# AbercrombieBlockage2.net
KiCad netlist of a schematic drawn in EAGLE
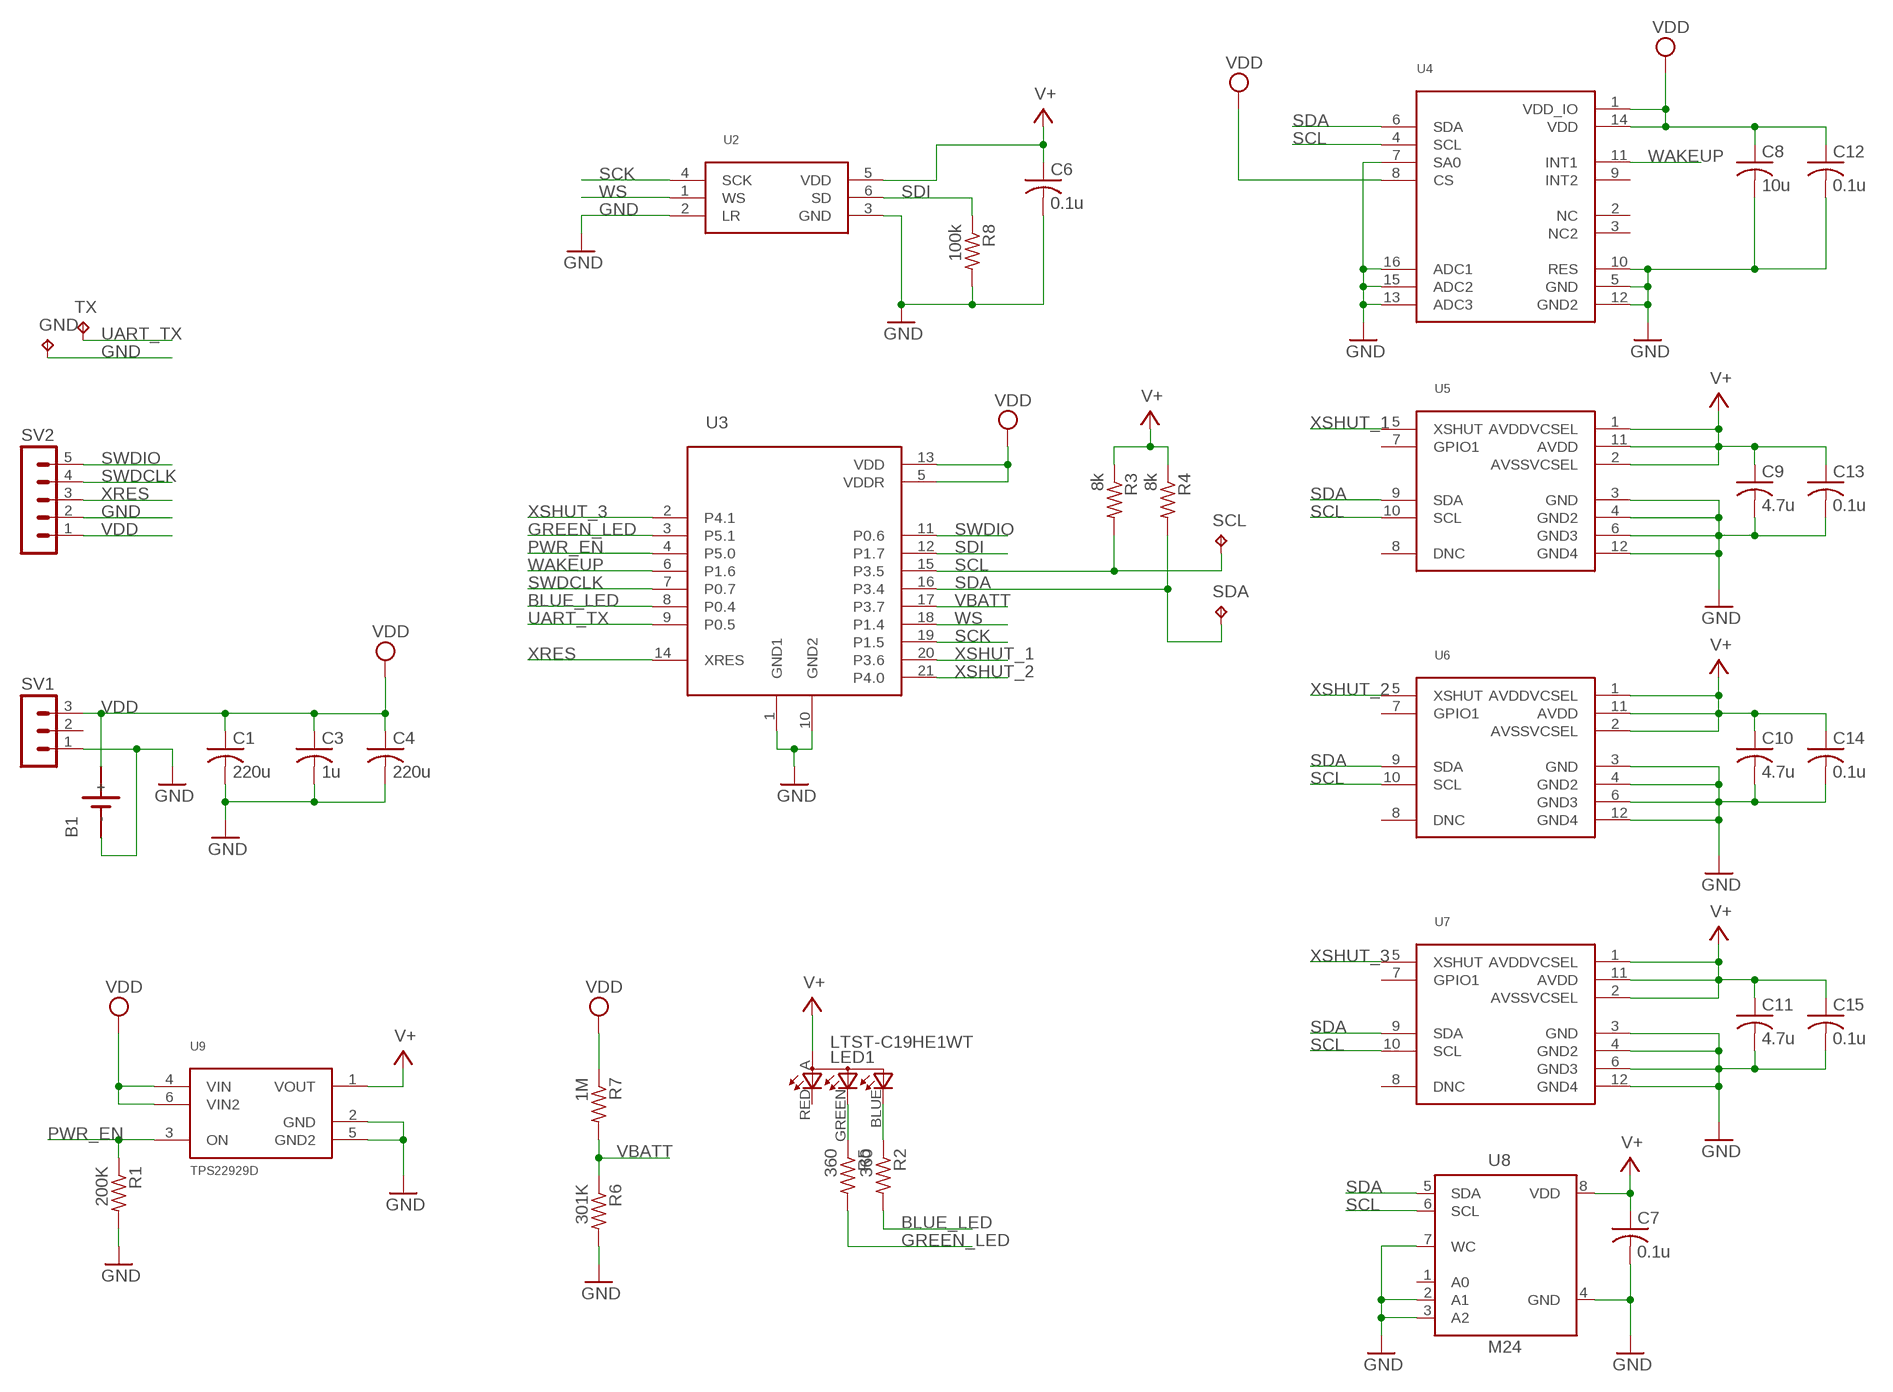
[diagram p0: schematic, sheet 1]

(export (version "E")
  (design (tool "Eeschema 10.0.6"))
  (components
    (comp (ref "B1")
      (value "BU2032")
      (footprint "eagle-import:BU2032")
      (libsource (lib "eagle-import") (part "BU2032"))
    )
    (comp (ref "C1")
      (value "220u")
      (footprint "eagle-import:C1210")
      (libsource (lib "eagle-import") (part "C-USC1210"))
    )
    (comp (ref "C3")
      (value "1u")
      (footprint "eagle-import:C0603")
      (libsource (lib "eagle-import") (part "C-USC0603"))
    )
    (comp (ref "C4")
      (value "220u")
      (footprint "eagle-import:C1210")
      (libsource (lib "eagle-import") (part "C-USC1210"))
    )
    (comp (ref "C6")
      (value "0.1u")
      (footprint "eagle-import:C0603")
      (libsource (lib "eagle-import") (part "C-USC0603"))
    )
    (comp (ref "C7")
      (value "0.1u")
      (footprint "eagle-import:C0603")
      (libsource (lib "eagle-import") (part "C-USC0603"))
    )
    (comp (ref "C8")
      (value "10u")
      (footprint "eagle-import:C0603")
      (libsource (lib "eagle-import") (part "C-USC0603"))
    )
    (comp (ref "C9")
      (value "4.7u")
      (footprint "eagle-import:C0603")
      (libsource (lib "eagle-import") (part "C-USC0603"))
    )
    (comp (ref "C10")
      (value "4.7u")
      (footprint "eagle-import:C0603")
      (libsource (lib "eagle-import") (part "C-USC0603"))
    )
    (comp (ref "C11")
      (value "4.7u")
      (footprint "eagle-import:C0603")
      (libsource (lib "eagle-import") (part "C-USC0603"))
    )
    (comp (ref "C12")
      (value "0.1u")
      (footprint "eagle-import:C0603")
      (libsource (lib "eagle-import") (part "C-USC0603"))
    )
    (comp (ref "C13")
      (value "0.1u")
      (footprint "eagle-import:C0603")
      (libsource (lib "eagle-import") (part "C-USC0603"))
    )
    (comp (ref "C14")
      (value "0.1u")
      (footprint "eagle-import:C0603")
      (libsource (lib "eagle-import") (part "C-USC0603"))
    )
    (comp (ref "C15")
      (value "0.1u")
      (footprint "eagle-import:C0603")
      (libsource (lib "eagle-import") (part "C-USC0603"))
    )
    (comp (ref "GND")
      (value "TPB1,27")
      (footprint "eagle-import:B1,27")
      (libsource (lib "eagle-import") (part "TPB1,27"))
    )
    (comp (ref "LED1")
      (value "LTST-C19HE1WT")
      (footprint "eagle-import:LTST-C19HE1WT")
      (libsource (lib "eagle-import") (part "LTST-C19HE1WT"))
    )
    (comp (ref "R1")
      (value "200K")
      (footprint "eagle-import:R0603")
      (libsource (lib "eagle-import") (part "R-US_R0603"))
    )
    (comp (ref "R2")
      (value "360")
      (footprint "eagle-import:R0603")
      (libsource (lib "eagle-import") (part "R-US_R0603"))
    )
    (comp (ref "R3")
      (value "8k")
      (footprint "eagle-import:R0603")
      (libsource (lib "eagle-import") (part "R-US_R0603"))
    )
    (comp (ref "R4")
      (value "8k")
      (footprint "eagle-import:R0603")
      (libsource (lib "eagle-import") (part "R-US_R0603"))
    )
    (comp (ref "R5")
      (value "360")
      (footprint "eagle-import:R0603")
      (libsource (lib "eagle-import") (part "R-US_R0603"))
    )
    (comp (ref "R6")
      (value "301K")
      (footprint "eagle-import:R0603")
      (libsource (lib "eagle-import") (part "R-US_R0603"))
    )
    (comp (ref "R7")
      (value "1M")
      (footprint "eagle-import:R0603")
      (libsource (lib "eagle-import") (part "R-US_R0603"))
    )
    (comp (ref "R8")
      (value "100k")
      (footprint "eagle-import:R0603")
      (libsource (lib "eagle-import") (part "R-US_R0603"))
    )
    (comp (ref "SCL")
      (value "TPB1,27")
      (footprint "eagle-import:B1,27")
      (libsource (lib "eagle-import") (part "TPB1,27"))
    )
    (comp (ref "SDA")
      (value "TPB1,27")
      (footprint "eagle-import:B1,27")
      (libsource (lib "eagle-import") (part "TPB1,27"))
    )
    (comp (ref "SV1")
      (value "MA03-1")
      (footprint "eagle-import:MA03-1")
      (libsource (lib "eagle-import") (part "MA03-1"))
    )
    (comp (ref "SV2")
      (value "MA05-1")
      (footprint "eagle-import:MA05-1")
      (libsource (lib "eagle-import") (part "MA05-1"))
    )
    (comp (ref "TX")
      (value "TPB1,27")
      (footprint "eagle-import:B1,27")
      (libsource (lib "eagle-import") (part "TPB1,27"))
    )
    (comp (ref "U2")
      (value "ICS-43434")
      (footprint "eagle-import:ICS-43434")
      (libsource (lib "eagle-import") (part "ICS-43434"))
    )
    (comp (ref "U3")
      (value "CYBLE-022001-00")
      (footprint "eagle-import:CYBLE-022001-00")
      (libsource (lib "eagle-import") (part "CYBLE-022001-00"))
    )
    (comp (ref "U4")
      (value "LIS3DH")
      (footprint "eagle-import:LGA-16")
      (libsource (lib "eagle-import") (part "LIS3DH"))
    )
    (comp (ref "U5")
      (value "VL53L0X")
      (footprint "eagle-import:VL53L0X")
      (libsource (lib "eagle-import") (part "VL53L0X"))
    )
    (comp (ref "U6")
      (value "VL53L0X")
      (footprint "eagle-import:VL53L0X")
      (libsource (lib "eagle-import") (part "VL53L0X"))
    )
    (comp (ref "U7")
      (value "VL53L0X")
      (footprint "eagle-import:VL53L0X")
      (libsource (lib "eagle-import") (part "VL53L0X"))
    )
    (comp (ref "U8")
      (value "M24")
      (footprint "eagle-import:SO-08")
      (libsource (lib "eagle-import") (part "M24"))
    )
    (comp (ref "U9")
      (value "TPS22929D")
      (footprint "eagle-import:SOT-23-6")
      (libsource (lib "eagle-import") (part "TPS22929D"))
    )
  )
  (nets
    (net (code "1") (name "/BLUE_LED") (class "Default")
      (node (ref "R2") (pin "2") (pinfunction "2_2") (pintype "passive"))
      (node (ref "U3") (pin "8") (pinfunction "P0.4_8") (pintype "bidirectional"))
    )
    (net (code "2") (name "/GREEN_LED") (class "Default")
      (node (ref "R5") (pin "2") (pinfunction "2_2") (pintype "passive"))
      (node (ref "U3") (pin "3") (pinfunction "P5.1_3") (pintype "bidirectional"))
    )
    (net (code "3") (name "/PWR_EN") (class "Default")
      (node (ref "R1") (pin "1") (pinfunction "1_1") (pintype "passive"))
      (node (ref "U3") (pin "4") (pinfunction "P5.0_4") (pintype "bidirectional"))
      (node (ref "U9") (pin "3") (pinfunction "ON_3") (pintype "bidirectional"))
    )
    (net (code "4") (name "/SCK") (class "Default")
      (node (ref "U2") (pin "4") (pinfunction "SCK_4") (pintype "bidirectional"))
      (node (ref "U3") (pin "19") (pinfunction "P1.5_19") (pintype "bidirectional"))
    )
    (net (code "5") (name "/SCL") (class "Default")
      (node (ref "R3") (pin "2") (pinfunction "2_2") (pintype "passive"))
      (node (ref "SCL") (pin "TP") (pinfunction "TP_TP") (pintype "input"))
      (node (ref "U3") (pin "15") (pinfunction "P3.5_15") (pintype "bidirectional"))
      (node (ref "U4") (pin "4") (pinfunction "SCL_4") (pintype "bidirectional"))
      (node (ref "U5") (pin "10") (pinfunction "SCL_10") (pintype "bidirectional"))
      (node (ref "U6") (pin "10") (pinfunction "SCL_10") (pintype "bidirectional"))
      (node (ref "U7") (pin "10") (pinfunction "SCL_10") (pintype "bidirectional"))
      (node (ref "U8") (pin "6") (pinfunction "SCL_6") (pintype "input"))
    )
    (net (code "6") (name "/SDA") (class "Default")
      (node (ref "R4") (pin "2") (pinfunction "2_2") (pintype "passive"))
      (node (ref "SDA") (pin "TP") (pinfunction "TP_TP") (pintype "input"))
      (node (ref "U3") (pin "16") (pinfunction "P3.4_16") (pintype "bidirectional"))
      (node (ref "U4") (pin "6") (pinfunction "SDA_6") (pintype "bidirectional"))
      (node (ref "U5") (pin "9") (pinfunction "SDA_9") (pintype "bidirectional"))
      (node (ref "U6") (pin "9") (pinfunction "SDA_9") (pintype "bidirectional"))
      (node (ref "U7") (pin "9") (pinfunction "SDA_9") (pintype "bidirectional"))
      (node (ref "U8") (pin "5") (pinfunction "SDA_5") (pintype "bidirectional"))
    )
    (net (code "7") (name "/SDI") (class "Default")
      (node (ref "R8") (pin "1") (pinfunction "1_1") (pintype "passive"))
      (node (ref "U2") (pin "6") (pinfunction "SD_6") (pintype "bidirectional"))
      (node (ref "U3") (pin "12") (pinfunction "P1.7_12") (pintype "bidirectional"))
    )
    (net (code "8") (name "/SWDCLK") (class "Default")
      (node (ref "SV2") (pin "4") (pinfunction "4_4") (pintype "passive"))
      (node (ref "U3") (pin "7") (pinfunction "P0.7_7") (pintype "bidirectional"))
    )
    (net (code "9") (name "/SWDIO") (class "Default")
      (node (ref "SV2") (pin "5") (pinfunction "5_5") (pintype "passive"))
      (node (ref "U3") (pin "11") (pinfunction "P0.6_11") (pintype "bidirectional"))
    )
    (net (code "10") (name "/UART_TX") (class "Default")
      (node (ref "TX") (pin "TP") (pinfunction "TP_TP") (pintype "input"))
      (node (ref "U3") (pin "9") (pinfunction "P0.5_9") (pintype "bidirectional"))
    )
    (net (code "11") (name "/VBATT") (class "Default")
      (node (ref "R6") (pin "1") (pinfunction "1_1") (pintype "passive"))
      (node (ref "R7") (pin "2") (pinfunction "2_2") (pintype "passive"))
      (node (ref "U3") (pin "17") (pinfunction "P3.7_17") (pintype "bidirectional"))
    )
    (net (code "12") (name "/WAKEUP") (class "Default")
      (node (ref "U3") (pin "6") (pinfunction "P1.6_6") (pintype "bidirectional"))
      (node (ref "U4") (pin "11") (pinfunction "INT1_11") (pintype "bidirectional"))
    )
    (net (code "13") (name "/WS") (class "Default")
      (node (ref "U2") (pin "1") (pinfunction "WS_1") (pintype "bidirectional"))
      (node (ref "U3") (pin "18") (pinfunction "P1.4_18") (pintype "bidirectional"))
    )
    (net (code "14") (name "/XRES") (class "Default")
      (node (ref "SV2") (pin "3") (pinfunction "3_3") (pintype "passive"))
      (node (ref "U3") (pin "14") (pinfunction "XRES_14") (pintype "bidirectional"))
    )
    (net (code "15") (name "/XSHUT_1") (class "Default")
      (node (ref "U3") (pin "20") (pinfunction "P3.6_20") (pintype "bidirectional"))
      (node (ref "U5") (pin "5") (pinfunction "XSHUT_5") (pintype "bidirectional"))
    )
    (net (code "16") (name "/XSHUT_2") (class "Default")
      (node (ref "U3") (pin "21") (pinfunction "P4.0_21") (pintype "bidirectional"))
      (node (ref "U6") (pin "5") (pinfunction "XSHUT_5") (pintype "bidirectional"))
    )
    (net (code "17") (name "/XSHUT_3") (class "Default")
      (node (ref "U3") (pin "2") (pinfunction "P4.1_2") (pintype "bidirectional"))
      (node (ref "U7") (pin "5") (pinfunction "XSHUT_5") (pintype "bidirectional"))
    )
    (net (code "18") (name "GND") (class "Default")
      (node (ref "B1") (pin "NEG") (pinfunction "-_NEG") (pintype "passive"))
      (node (ref "C1") (pin "2") (pinfunction "2_2") (pintype "passive"))
      (node (ref "C10") (pin "2") (pinfunction "2_2") (pintype "passive"))
      (node (ref "C11") (pin "2") (pinfunction "2_2") (pintype "passive"))
      (node (ref "C12") (pin "2") (pinfunction "2_2") (pintype "passive"))
      (node (ref "C13") (pin "2") (pinfunction "2_2") (pintype "passive"))
      (node (ref "C14") (pin "2") (pinfunction "2_2") (pintype "passive"))
      (node (ref "C15") (pin "2") (pinfunction "2_2") (pintype "passive"))
      (node (ref "C3") (pin "2") (pinfunction "2_2") (pintype "passive"))
      (node (ref "C4") (pin "2") (pinfunction "2_2") (pintype "passive"))
      (node (ref "C6") (pin "2") (pinfunction "2_2") (pintype "passive"))
      (node (ref "C7") (pin "2") (pinfunction "2_2") (pintype "passive"))
      (node (ref "C8") (pin "2") (pinfunction "2_2") (pintype "passive"))
      (node (ref "C9") (pin "2") (pinfunction "2_2") (pintype "passive"))
      (node (ref "GND") (pin "TP") (pinfunction "TP_TP") (pintype "input"))
      (node (ref "R1") (pin "2") (pinfunction "2_2") (pintype "passive"))
      (node (ref "R6") (pin "2") (pinfunction "2_2") (pintype "passive"))
      (node (ref "R8") (pin "2") (pinfunction "2_2") (pintype "passive"))
      (node (ref "SV1") (pin "1") (pinfunction "1_1") (pintype "passive"))
      (node (ref "SV2") (pin "2") (pinfunction "2_2") (pintype "passive"))
      (node (ref "U2") (pin "2") (pinfunction "LR_2") (pintype "bidirectional"))
      (node (ref "U2") (pin "3") (pinfunction "GND_3") (pintype "bidirectional"))
      (node (ref "U3") (pin "1") (pinfunction "GND1_1") (pintype "bidirectional"))
      (node (ref "U3") (pin "10") (pinfunction "GND2_10") (pintype "bidirectional"))
      (node (ref "U4") (pin "10") (pinfunction "RES_10") (pintype "bidirectional"))
      (node (ref "U4") (pin "12") (pinfunction "GND2_12") (pintype "bidirectional"))
      (node (ref "U4") (pin "13") (pinfunction "ADC3_13") (pintype "bidirectional"))
      (node (ref "U4") (pin "15") (pinfunction "ADC2_15") (pintype "bidirectional"))
      (node (ref "U4") (pin "16") (pinfunction "ADC1_16") (pintype "bidirectional"))
      (node (ref "U4") (pin "5") (pinfunction "GND_5") (pintype "bidirectional"))
      (node (ref "U4") (pin "7") (pinfunction "SA0_7") (pintype "bidirectional"))
      (node (ref "U5") (pin "12") (pinfunction "GND4_12") (pintype "bidirectional"))
      (node (ref "U5") (pin "3") (pinfunction "GND_3") (pintype "bidirectional"))
      (node (ref "U5") (pin "4") (pinfunction "GND2_4") (pintype "bidirectional"))
      (node (ref "U5") (pin "6") (pinfunction "GND3_6") (pintype "bidirectional"))
      (node (ref "U6") (pin "12") (pinfunction "GND4_12") (pintype "bidirectional"))
      (node (ref "U6") (pin "3") (pinfunction "GND_3") (pintype "bidirectional"))
      (node (ref "U6") (pin "4") (pinfunction "GND2_4") (pintype "bidirectional"))
      (node (ref "U6") (pin "6") (pinfunction "GND3_6") (pintype "bidirectional"))
      (node (ref "U7") (pin "12") (pinfunction "GND4_12") (pintype "bidirectional"))
      (node (ref "U7") (pin "3") (pinfunction "GND_3") (pintype "bidirectional"))
      (node (ref "U7") (pin "4") (pinfunction "GND2_4") (pintype "bidirectional"))
      (node (ref "U7") (pin "6") (pinfunction "GND3_6") (pintype "bidirectional"))
      (node (ref "U8") (pin "2") (pinfunction "A1_2") (pintype "input"))
      (node (ref "U8") (pin "3") (pinfunction "A2_3") (pintype "input"))
      (node (ref "U8") (pin "4") (pinfunction "GND_4") (pintype "power_in"))
      (node (ref "U8") (pin "7") (pinfunction "WC_7") (pintype "input"))
      (node (ref "U9") (pin "2") (pinfunction "GND_2") (pintype "bidirectional"))
      (node (ref "U9") (pin "5") (pinfunction "GND2_5") (pintype "bidirectional"))
    )
    (net (code "19") (name "Net-(LED1-CBLUE)") (class "Default")
      (node (ref "LED1") (pin "BLUE") (pinfunction "CBLUE_BLUE") (pintype "passive"))
      (node (ref "R2") (pin "1") (pinfunction "1_1") (pintype "passive"))
    )
    (net (code "20") (name "Net-(LED1-CGREEN)") (class "Default")
      (node (ref "LED1") (pin "GREEN") (pinfunction "CGREEN_GREEN") (pintype "passive"))
      (node (ref "R5") (pin "1") (pinfunction "1_1") (pintype "passive"))
    )
    (net (code "21") (name "V+") (class "Default")
      (node (ref "C10") (pin "1") (pinfunction "1_1") (pintype "passive"))
      (node (ref "C11") (pin "1") (pinfunction "1_1") (pintype "passive"))
      (node (ref "C13") (pin "1") (pinfunction "1_1") (pintype "passive"))
      (node (ref "C14") (pin "1") (pinfunction "1_1") (pintype "passive"))
      (node (ref "C15") (pin "1") (pinfunction "1_1") (pintype "passive"))
      (node (ref "C6") (pin "1") (pinfunction "1_1") (pintype "passive"))
      (node (ref "C7") (pin "1") (pinfunction "1_1") (pintype "passive"))
      (node (ref "C9") (pin "1") (pinfunction "1_1") (pintype "passive"))
      (node (ref "LED1") (pin "A") (pinfunction "A_A") (pintype "passive"))
      (node (ref "R3") (pin "1") (pinfunction "1_1") (pintype "passive"))
      (node (ref "R4") (pin "1") (pinfunction "1_1") (pintype "passive"))
      (node (ref "U2") (pin "5") (pinfunction "VDD_5") (pintype "bidirectional"))
      (node (ref "U5") (pin "1") (pinfunction "AVDDVCSEL_1") (pintype "bidirectional"))
      (node (ref "U5") (pin "11") (pinfunction "AVDD_11") (pintype "bidirectional"))
      (node (ref "U5") (pin "2") (pinfunction "AVSSVCSEL_2") (pintype "bidirectional"))
      (node (ref "U6") (pin "1") (pinfunction "AVDDVCSEL_1") (pintype "bidirectional"))
      (node (ref "U6") (pin "11") (pinfunction "AVDD_11") (pintype "bidirectional"))
      (node (ref "U6") (pin "2") (pinfunction "AVSSVCSEL_2") (pintype "bidirectional"))
      (node (ref "U7") (pin "1") (pinfunction "AVDDVCSEL_1") (pintype "bidirectional"))
      (node (ref "U7") (pin "11") (pinfunction "AVDD_11") (pintype "bidirectional"))
      (node (ref "U7") (pin "2") (pinfunction "AVSSVCSEL_2") (pintype "bidirectional"))
      (node (ref "U8") (pin "8") (pinfunction "VDD_8") (pintype "power_in"))
      (node (ref "U9") (pin "1") (pinfunction "VOUT_1") (pintype "bidirectional"))
    )
    (net (code "22") (name "VDD") (class "Default")
      (node (ref "B1") (pin "PLUS") (pinfunction "+_PLUS") (pintype "passive"))
      (node (ref "C1") (pin "1") (pinfunction "1_1") (pintype "passive"))
      (node (ref "C12") (pin "1") (pinfunction "1_1") (pintype "passive"))
      (node (ref "C3") (pin "1") (pinfunction "1_1") (pintype "passive"))
      (node (ref "C4") (pin "1") (pinfunction "1_1") (pintype "passive"))
      (node (ref "C8") (pin "1") (pinfunction "1_1") (pintype "passive"))
      (node (ref "R7") (pin "1") (pinfunction "1_1") (pintype "passive"))
      (node (ref "SV1") (pin "3") (pinfunction "3_3") (pintype "passive"))
      (node (ref "SV2") (pin "1") (pinfunction "1_1") (pintype "passive"))
      (node (ref "U3") (pin "13") (pinfunction "VDD_13") (pintype "bidirectional"))
      (node (ref "U3") (pin "5") (pinfunction "VDDR_5") (pintype "bidirectional"))
      (node (ref "U4") (pin "1") (pinfunction "VDD_IO_1") (pintype "bidirectional"))
      (node (ref "U4") (pin "14") (pinfunction "VDD_14") (pintype "bidirectional"))
      (node (ref "U4") (pin "8") (pinfunction "CS_8") (pintype "bidirectional"))
      (node (ref "U9") (pin "4") (pinfunction "VIN_4") (pintype "bidirectional"))
      (node (ref "U9") (pin "6") (pinfunction "VIN2_6") (pintype "bidirectional"))
    )
    (net (code "23") (name "unconnected-(LED1-CRED-PadRED)") (class "Default")
      (node (ref "LED1") (pin "RED") (pinfunction "CRED_RED") (pintype "passive"))
    )
    (net (code "24") (name "unconnected-(SV1-Pad2)") (class "Default")
      (node (ref "SV1") (pin "2") (pinfunction "2_2") (pintype "passive"))
    )
    (net (code "25") (name "unconnected-(U4-INT2-Pad9)") (class "Default")
      (node (ref "U4") (pin "9") (pinfunction "INT2_9") (pintype "bidirectional"))
    )
    (net (code "26") (name "unconnected-(U4-NC-Pad2)") (class "Default")
      (node (ref "U4") (pin "2") (pinfunction "NC_2") (pintype "bidirectional"))
    )
    (net (code "27") (name "unconnected-(U4-NC2-Pad3)") (class "Default")
      (node (ref "U4") (pin "3") (pinfunction "NC2_3") (pintype "bidirectional"))
    )
    (net (code "28") (name "unconnected-(U5-DNC-Pad8)") (class "Default")
      (node (ref "U5") (pin "8") (pinfunction "DNC_8") (pintype "bidirectional"))
    )
    (net (code "29") (name "unconnected-(U5-GPIO1-Pad7)") (class "Default")
      (node (ref "U5") (pin "7") (pinfunction "GPIO1_7") (pintype "bidirectional"))
    )
    (net (code "30") (name "unconnected-(U6-DNC-Pad8)") (class "Default")
      (node (ref "U6") (pin "8") (pinfunction "DNC_8") (pintype "bidirectional"))
    )
    (net (code "31") (name "unconnected-(U6-GPIO1-Pad7)") (class "Default")
      (node (ref "U6") (pin "7") (pinfunction "GPIO1_7") (pintype "bidirectional"))
    )
    (net (code "32") (name "unconnected-(U7-DNC-Pad8)") (class "Default")
      (node (ref "U7") (pin "8") (pinfunction "DNC_8") (pintype "bidirectional"))
    )
    (net (code "33") (name "unconnected-(U7-GPIO1-Pad7)") (class "Default")
      (node (ref "U7") (pin "7") (pinfunction "GPIO1_7") (pintype "bidirectional"))
    )
    (net (code "34") (name "unconnected-(U8-A0-Pad1)") (class "Default")
      (node (ref "U8") (pin "1") (pinfunction "A0_1") (pintype "input"))
    )
  )
)
